# Sheet4.net
KiCad netlist of a schematic drawn in Altium Designer
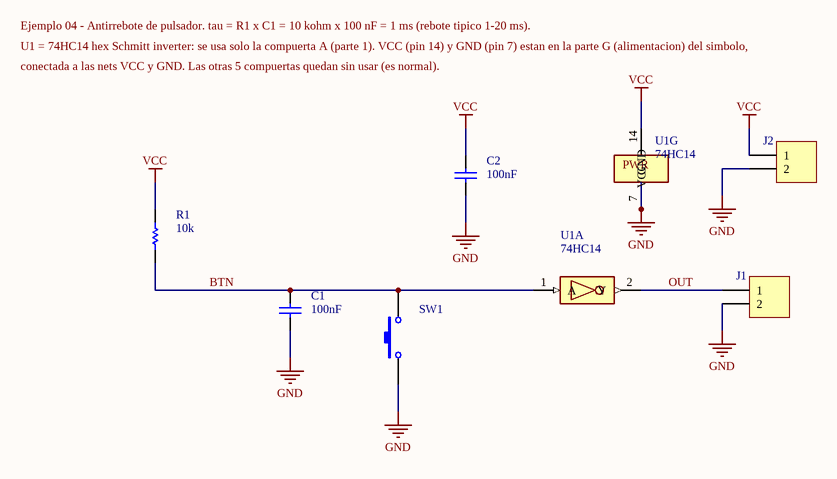
[diagram p0: Sheet4.SchDoc]

(export (version "E")
  (design (tool "Eeschema 10.0.6"))
  (components
    (comp (ref "C1")
      (value "100nF")
      (footprint "RAD-0.3")
      (description "Ceramic capacitor 100 nF (debounce)")
      (fields
        (field (name "MANUFACTURER") "KEMET")
        (field (name "MANUFACTURER PART NUMBER") "C320C104K5R5TA")
        (field (name "PUBLISHER") "Altium Limited")
      )
      (libsource (lib "Miscellaneous Devices") (part "Cap"))
    )
    (comp (ref "C2")
      (value "100nF")
      (footprint "RAD-0.3")
      (description "Ceramic capacitor 100 nF (decoupling of U1)")
      (fields
        (field (name "MANUFACTURER") "KEMET")
        (field (name "MANUFACTURER PART NUMBER") "C320C104K5R5TA")
        (field (name "PUBLISHER") "Altium Limited")
      )
      (libsource (lib "Miscellaneous Devices") (part "Cap"))
    )
    (comp (ref "J1")
      (value "Header 2")
      (footprint "HDR1X2")
      (description "Header 2 pin, 2.54 mm: clean output (OUT, GND)")
      (fields
        (field (name "MANUFACTURER") "Generic")
        (field (name "MANUFACTURER PART NUMBER") "Pin header 1x2")
        (field (name "PUBLISHER") "Altium Limited")
      )
      (libsource (lib "Miscellaneous Connectors") (part "Header 2"))
    )
    (comp (ref "J2")
      (value "Header 2")
      (footprint "HDR1X2")
      (description "Header 2 pin, 2.54 mm: power input (VCC, GND)")
      (fields
        (field (name "MANUFACTURER") "Generic")
        (field (name "MANUFACTURER PART NUMBER") "Pin header 1x2")
        (field (name "PUBLISHER") "Altium Limited")
      )
      (libsource (lib "Miscellaneous Connectors") (part "Header 2"))
    )
    (comp (ref "R1")
      (value "10k")
      (footprint "AXIAL-0.3")
      (description "Resistor 10 kohm 1/4 W, pull-up")
      (fields
        (field (name "MANUFACTURER") "Yageo")
        (field (name "MANUFACTURER PART NUMBER") "CFR-25JB-52-10K")
        (field (name "PUBLISHER") "Altium Limited")
      )
      (libsource (lib "Miscellaneous Devices") (part "Res1"))
    )
    (comp (ref "SW1")
      (value "SW-PB")
      (footprint "SPST-2")
      (description "Push button, normally open")
      (fields
        (field (name "MANUFACTURER") "Generic")
        (field (name "MANUFACTURER PART NUMBER") "Tactile switch 6x6")
        (field (name "PUBLISHER") "Altium Limited")
      )
      (libsource (lib "Miscellaneous Devices") (part "SW-PB"))
    )
    (comp (ref "U1")
      (value "74HC14")
      (footprint "DIP-14")
      (description "Hex Schmitt-trigger inverter (gate A used)")
      (fields
        (field (name "MANUFACTURER") "Texas Instruments")
        (field (name "MANUFACTURER PART NUMBER") "SN74HC14N")
      )
      (libsource (lib "*") (part "74HC14"))
    )
  )
  (nets
    (net (code "1") (name "/BTN") (class "Default")
      (node (ref "C1") (pin "2") (pinfunction "2_2") (pintype "passive"))
      (node (ref "R1") (pin "1") (pinfunction "1_1") (pintype "passive"))
      (node (ref "SW1") (pin "2") (pinfunction "2_2") (pintype "passive"))
      (node (ref "U1") (pin "1") (pinfunction "A_1") (pintype "input"))
    )
    (net (code "2") (name "/OUT") (class "Default")
      (node (ref "J1") (pin "1") (pinfunction "1_1") (pintype "passive"))
      (node (ref "U1") (pin "2") (pinfunction "Y_2") (pintype "output"))
    )
    (net (code "3") (name "GND") (class "Default")
      (node (ref "C1") (pin "1") (pinfunction "1_1") (pintype "passive"))
      (node (ref "C2") (pin "1") (pinfunction "1_1") (pintype "passive"))
      (node (ref "J1") (pin "2") (pinfunction "2_2") (pintype "passive"))
      (node (ref "J2") (pin "2") (pinfunction "2_2") (pintype "passive"))
      (node (ref "SW1") (pin "1") (pinfunction "1_1") (pintype "passive"))
      (node (ref "U1") (pin "7") (pinfunction "GND_7") (pintype "power_in"))
    )
    (net (code "4") (name "VCC") (class "Default")
      (node (ref "C2") (pin "2") (pinfunction "2_2") (pintype "passive"))
      (node (ref "J2") (pin "1") (pinfunction "1_1") (pintype "passive"))
      (node (ref "R1") (pin "2") (pinfunction "2_2") (pintype "passive"))
      (node (ref "U1") (pin "14") (pinfunction "VCC_14") (pintype "power_in"))
    )
  )
)
